# duck_esp.net
KiCad netlist of a schematic drawn in EAGLE
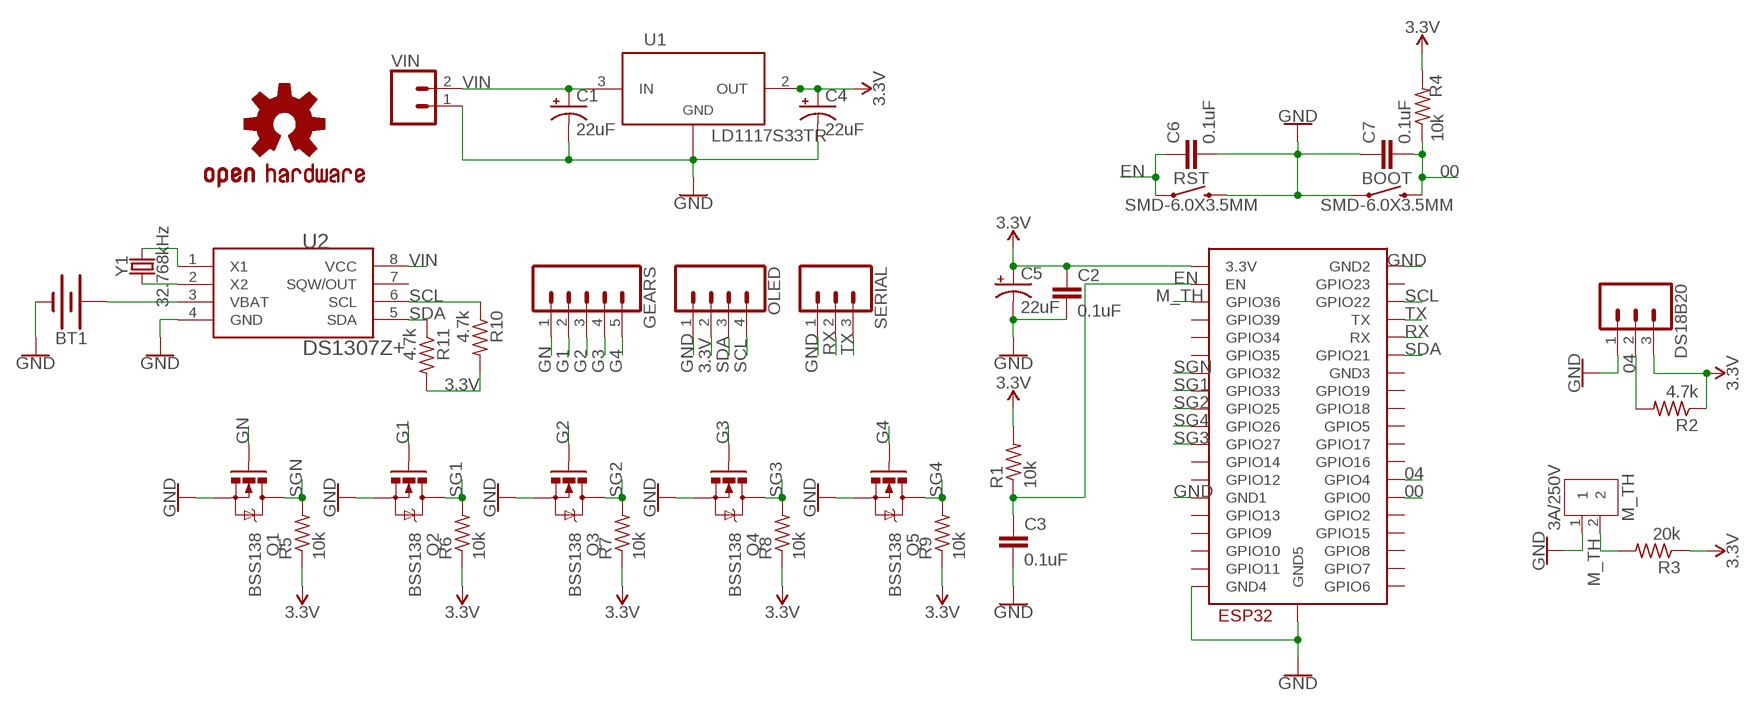
[diagram p0: schematic, sheet 1]

(export (version "E")
  (design (tool "Eeschema 10.0.6"))
  (components
    (comp (ref "BOOT")
      (value "SMD-6.0X3.5MM")
      (footprint "eagle-import:TACTILE_SWITCH_SMD_6.0X3.5MM")
      (libsource (lib "eagle-import") (part "MOMENTARY-SWITCH-SPST-SMD-6.0X3.5MM"))
    )
    (comp (ref "BT1")
      (value "BATTERY-12MM_SMD")
      (footprint "eagle-import:BATTCON_12MM")
      (libsource (lib "eagle-import") (part "BATTERY-12MM_SMD"))
    )
    (comp (ref "C1")
      (value "22uF")
      (footprint "eagle-import:E2-5")
      (libsource (lib "eagle-import") (part "CPOL-USE2-5"))
    )
    (comp (ref "C2")
      (value "0.1uF")
      (footprint "eagle-import:0805")
      (libsource (lib "eagle-import") (part "22UF-0805-6.3V-20%"))
    )
    (comp (ref "C3")
      (value "0.1uF")
      (footprint "eagle-import:0805")
      (libsource (lib "eagle-import") (part "22UF-0805-6.3V-20%"))
    )
    (comp (ref "C4")
      (value "22uF")
      (footprint "eagle-import:E2-5")
      (libsource (lib "eagle-import") (part "CPOL-USE2-5"))
    )
    (comp (ref "C5")
      (value "22uF")
      (footprint "eagle-import:E2-5")
      (libsource (lib "eagle-import") (part "CPOL-USE2-5"))
    )
    (comp (ref "C6")
      (value "0.1uF")
      (footprint "eagle-import:0805")
      (libsource (lib "eagle-import") (part "22UF-0805-6.3V-20%"))
    )
    (comp (ref "C7")
      (value "0.1uF")
      (footprint "eagle-import:0805")
      (libsource (lib "eagle-import") (part "22UF-0805-6.3V-20%"))
    )
    (comp (ref "DS18B20")
      (value "CONN_03")
      (footprint "eagle-import:1X03")
      (libsource (lib "eagle-import") (part "CONN_03"))
    )
    (comp (ref "GEARS")
      (value "CONN_05")
      (footprint "eagle-import:1X05")
      (libsource (lib "eagle-import") (part "CONN_05"))
    )
    (comp (ref "LOGO1")
      (value "OSHW-LOGOL-COPPER")
      (footprint "eagle-import:OSHW-LOGO-L_COPPER")
      (libsource (lib "eagle-import") (part "OSHW-LOGOL-COPPER"))
    )
    (comp (ref "M_TH")
      (value "3A/250V")
      (footprint "eagle-import:B2B-XH-A")
      (fields (field (name "MANUFACTURER") "JST (XH CONNECTOR)") (field (name "MPN") "B2B-XH-A"))
      (libsource (lib "eagle-import") (part "B2B-XH-A"))
    )
    (comp (ref "OLED")
      (value "CONN_04")
      (footprint "eagle-import:1X04")
      (libsource (lib "eagle-import") (part "CONN_04"))
    )
    (comp (ref "Q1")
      (value "BSS138")
      (footprint "eagle-import:SOT23")
      (libsource (lib "eagle-import") (part "MOSFET-NCHANNELBSS138"))
    )
    (comp (ref "Q2")
      (value "BSS138")
      (footprint "eagle-import:SOT23")
      (libsource (lib "eagle-import") (part "MOSFET-NCHANNELBSS138"))
    )
    (comp (ref "Q3")
      (value "BSS138")
      (footprint "eagle-import:SOT23")
      (libsource (lib "eagle-import") (part "MOSFET-NCHANNELBSS138"))
    )
    (comp (ref "Q4")
      (value "BSS138")
      (footprint "eagle-import:SOT23")
      (libsource (lib "eagle-import") (part "MOSFET-NCHANNELBSS138"))
    )
    (comp (ref "Q5")
      (value "BSS138")
      (footprint "eagle-import:SOT23")
      (libsource (lib "eagle-import") (part "MOSFET-NCHANNELBSS138"))
    )
    (comp (ref "R1")
      (value "10k")
      (footprint "eagle-import:R0805")
      (libsource (lib "eagle-import") (part "R-US_R0805"))
    )
    (comp (ref "R2")
      (value "4.7k")
      (footprint "eagle-import:R0805")
      (libsource (lib "eagle-import") (part "R-US_R0805"))
    )
    (comp (ref "R3")
      (value "20k")
      (footprint "eagle-import:R0805")
      (libsource (lib "eagle-import") (part "R-US_R0805"))
    )
    (comp (ref "R4")
      (value "10k")
      (footprint "eagle-import:R0805")
      (libsource (lib "eagle-import") (part "R-US_R0805"))
    )
    (comp (ref "R5")
      (value "10k")
      (footprint "eagle-import:R0805")
      (libsource (lib "eagle-import") (part "R-US_R0805"))
    )
    (comp (ref "R6")
      (value "10k")
      (footprint "eagle-import:R0805")
      (libsource (lib "eagle-import") (part "R-US_R0805"))
    )
    (comp (ref "R7")
      (value "10k")
      (footprint "eagle-import:R0805")
      (libsource (lib "eagle-import") (part "R-US_R0805"))
    )
    (comp (ref "R8")
      (value "10k")
      (footprint "eagle-import:R0805")
      (libsource (lib "eagle-import") (part "R-US_R0805"))
    )
    (comp (ref "R9")
      (value "10k")
      (footprint "eagle-import:R0805")
      (libsource (lib "eagle-import") (part "R-US_R0805"))
    )
    (comp (ref "R10")
      (value "4.7k")
      (footprint "eagle-import:R0805")
      (libsource (lib "eagle-import") (part "R-US_R0805"))
    )
    (comp (ref "R11")
      (value "4.7k")
      (footprint "eagle-import:R0805")
      (libsource (lib "eagle-import") (part "R-US_R0805"))
    )
    (comp (ref "RST")
      (value "SMD-6.0X3.5MM")
      (footprint "eagle-import:TACTILE_SWITCH_SMD_6.0X3.5MM")
      (libsource (lib "eagle-import") (part "MOMENTARY-SWITCH-SPST-SMD-6.0X3.5MM"))
    )
    (comp (ref "SERIAL")
      (value "CONN_03")
      (footprint "eagle-import:1X03")
      (libsource (lib "eagle-import") (part "CONN_03"))
    )
    (comp (ref "U$1")
      (value "ESP32-WROOM")
      (footprint "eagle-import:ESP32-WROOM")
      (libsource (lib "eagle-import") (part "ESP32-WROOM"))
    )
    (comp (ref "U1")
      (value "LD1117S33TR")
      (footprint "eagle-import:SOT-223")
      (fields
        (field (name "DIGIKEY_PART_NUMBER") "497-1242-2-ND")
        (field (name "MANUFACTURER") "STMicroelectronics")
        (field (name "CREATED_BY") "PCBLayout.com")
      )
      (libsource (lib "eagle-import") (part "LD1117S33TR"))
    )
    (comp (ref "U2")
      (value "DS1307Z+")
      (footprint "eagle-import:SOIC-8N")
      (fields
        (field (name "DIGI-KEY_PART_NUMBER") "DS1307Z+-ND")
        (field (name "MANUFACTURER") "Maxim Integrated")
        (field (name "CREATED_BY") "PCBLayout.com")
      )
      (libsource (lib "eagle-import") (part "DS1307Z+"))
    )
    (comp (ref "VIN")
      (value "CONN_02POLAR")
      (footprint "eagle-import:MOLEX-1X2")
      (libsource (lib "eagle-import") (part "CONN_02POLAR"))
    )
    (comp (ref "Y1")
      (value "32.768kHz")
      (footprint "eagle-import:CRYSTAL-SMD-2X6-CYL")
      (libsource (lib "eagle-import") (part "CRYSTAL-32.768KHZSMD-2X6"))
    )
  )
  (nets
    (net (code "1") (name "/00") (class "Default")
      (node (ref "BOOT") (pin "2") (pinfunction "2_2") (pintype "passive"))
      (node (ref "C7") (pin "2") (pinfunction "2_2") (pintype "passive"))
      (node (ref "R4") (pin "1") (pinfunction "1_1") (pintype "passive"))
      (node (ref "U$1") (pin "IO0") (pinfunction "GPIO0_IO0") (pintype "bidirectional"))
    )
    (net (code "2") (name "/04") (class "Default")
      (node (ref "DS18B20") (pin "2") (pinfunction "2_2") (pintype "passive"))
      (node (ref "R2") (pin "2") (pinfunction "2_2") (pintype "passive"))
      (node (ref "U$1") (pin "IO4") (pinfunction "GPIO4_IO4") (pintype "bidirectional"))
    )
    (net (code "3") (name "/EN") (class "Default")
      (node (ref "C3") (pin "1") (pinfunction "1_1") (pintype "passive"))
      (node (ref "C6") (pin "1") (pinfunction "1_1") (pintype "passive"))
      (node (ref "R1") (pin "1") (pinfunction "1_1") (pintype "passive"))
      (node (ref "RST") (pin "1") (pinfunction "1_1") (pintype "passive"))
      (node (ref "U$1") (pin "EN") (pinfunction "EN_EN") (pintype "bidirectional"))
    )
    (net (code "4") (name "/G1") (class "Default")
      (node (ref "GEARS") (pin "2") (pinfunction "2_2") (pintype "passive"))
      (node (ref "Q2") (pin "1") (pinfunction "G_1") (pintype "passive"))
    )
    (net (code "5") (name "/G2") (class "Default")
      (node (ref "GEARS") (pin "3") (pinfunction "3_3") (pintype "passive"))
      (node (ref "Q3") (pin "1") (pinfunction "G_1") (pintype "passive"))
    )
    (net (code "6") (name "/G3") (class "Default")
      (node (ref "GEARS") (pin "4") (pinfunction "4_4") (pintype "passive"))
      (node (ref "Q4") (pin "1") (pinfunction "G_1") (pintype "passive"))
    )
    (net (code "7") (name "/G4") (class "Default")
      (node (ref "GEARS") (pin "5") (pinfunction "5_5") (pintype "passive"))
      (node (ref "Q5") (pin "1") (pinfunction "G_1") (pintype "passive"))
    )
    (net (code "8") (name "/GN") (class "Default")
      (node (ref "GEARS") (pin "1") (pinfunction "1_1") (pintype "passive"))
      (node (ref "Q1") (pin "1") (pinfunction "G_1") (pintype "passive"))
    )
    (net (code "9") (name "/M_TH") (class "Default")
      (node (ref "M_TH") (pin "2") (pinfunction "2_2") (pintype "bidirectional"))
      (node (ref "R3") (pin "2") (pinfunction "2_2") (pintype "passive"))
      (node (ref "U$1") (pin "SENSOR_VP") (pinfunction "GPIO36_SENSOR_VP") (pintype "bidirectional"))
    )
    (net (code "10") (name "/RX") (class "Default")
      (node (ref "SERIAL") (pin "2") (pinfunction "2_2") (pintype "passive"))
      (node (ref "U$1") (pin "RX") (pinfunction "RX_RX") (pintype "bidirectional"))
    )
    (net (code "11") (name "/SCL") (class "Default")
      (node (ref "OLED") (pin "4") (pinfunction "4_4") (pintype "passive"))
      (node (ref "R10") (pin "1") (pinfunction "1_1") (pintype "passive"))
      (node (ref "U$1") (pin "IO22") (pinfunction "GPIO22_IO22") (pintype "bidirectional"))
      (node (ref "U2") (pin "6") (pinfunction "SCL_6") (pintype "input"))
    )
    (net (code "12") (name "/SDA") (class "Default")
      (node (ref "OLED") (pin "3") (pinfunction "3_3") (pintype "passive"))
      (node (ref "R11") (pin "1") (pinfunction "1_1") (pintype "passive"))
      (node (ref "U$1") (pin "IO21") (pinfunction "GPIO21_IO21") (pintype "bidirectional"))
      (node (ref "U2") (pin "5") (pinfunction "SDA_5") (pintype "bidirectional"))
    )
    (net (code "13") (name "/SG1") (class "Default")
      (node (ref "Q2") (pin "3") (pinfunction "D_3") (pintype "passive"))
      (node (ref "R6") (pin "2") (pinfunction "2_2") (pintype "passive"))
      (node (ref "U$1") (pin "IO33") (pinfunction "GPIO33_IO33") (pintype "bidirectional"))
    )
    (net (code "14") (name "/SG2") (class "Default")
      (node (ref "Q3") (pin "3") (pinfunction "D_3") (pintype "passive"))
      (node (ref "R7") (pin "2") (pinfunction "2_2") (pintype "passive"))
      (node (ref "U$1") (pin "IO25") (pinfunction "GPIO25_IO25") (pintype "bidirectional"))
    )
    (net (code "15") (name "/SG3") (class "Default")
      (node (ref "Q4") (pin "3") (pinfunction "D_3") (pintype "passive"))
      (node (ref "R8") (pin "2") (pinfunction "2_2") (pintype "passive"))
      (node (ref "U$1") (pin "IO27") (pinfunction "GPIO27_IO27") (pintype "bidirectional"))
    )
    (net (code "16") (name "/SG4") (class "Default")
      (node (ref "Q5") (pin "3") (pinfunction "D_3") (pintype "passive"))
      (node (ref "R9") (pin "2") (pinfunction "2_2") (pintype "passive"))
      (node (ref "U$1") (pin "IO26") (pinfunction "GPIO26_IO26") (pintype "bidirectional"))
    )
    (net (code "17") (name "/SGN") (class "Default")
      (node (ref "Q1") (pin "3") (pinfunction "D_3") (pintype "passive"))
      (node (ref "R5") (pin "2") (pinfunction "2_2") (pintype "passive"))
      (node (ref "U$1") (pin "IO32") (pinfunction "GPIO32_IO32") (pintype "bidirectional"))
    )
    (net (code "18") (name "/TX") (class "Default")
      (node (ref "SERIAL") (pin "3") (pinfunction "3_3") (pintype "passive"))
      (node (ref "U$1") (pin "TX") (pinfunction "TX_TX") (pintype "bidirectional"))
    )
    (net (code "19") (name "/VIN") (class "Default")
      (node (ref "C1") (pin "+") (pinfunction "+_+") (pintype "passive"))
      (node (ref "U1") (pin "3") (pinfunction "IN_3") (pintype "input"))
      (node (ref "U2") (pin "8") (pinfunction "VCC_8") (pintype "power_in"))
      (node (ref "VIN") (pin "2") (pinfunction "2_2") (pintype "passive"))
    )
    (net (code "20") (name "3.3V") (class "Default")
      (node (ref "C2") (pin "1") (pinfunction "1_1") (pintype "passive"))
      (node (ref "C4") (pin "+") (pinfunction "+_+") (pintype "passive"))
      (node (ref "C5") (pin "+") (pinfunction "+_+") (pintype "passive"))
      (node (ref "DS18B20") (pin "3") (pinfunction "3_3") (pintype "passive"))
      (node (ref "OLED") (pin "2") (pinfunction "2_2") (pintype "passive"))
      (node (ref "R1") (pin "2") (pinfunction "2_2") (pintype "passive"))
      (node (ref "R10") (pin "2") (pinfunction "2_2") (pintype "passive"))
      (node (ref "R11") (pin "2") (pinfunction "2_2") (pintype "passive"))
      (node (ref "R2") (pin "1") (pinfunction "1_1") (pintype "passive"))
      (node (ref "R3") (pin "1") (pinfunction "1_1") (pintype "passive"))
      (node (ref "R4") (pin "2") (pinfunction "2_2") (pintype "passive"))
      (node (ref "R5") (pin "1") (pinfunction "1_1") (pintype "passive"))
      (node (ref "R6") (pin "1") (pinfunction "1_1") (pintype "passive"))
      (node (ref "R7") (pin "1") (pinfunction "1_1") (pintype "passive"))
      (node (ref "R8") (pin "1") (pinfunction "1_1") (pintype "passive"))
      (node (ref "R9") (pin "1") (pinfunction "1_1") (pintype "passive"))
      (node (ref "U$1") (pin "3V3") (pinfunction "3.3V_3V3") (pintype "bidirectional"))
      (node (ref "U1") (pin "2") (pinfunction "OUT_2") (pintype "output"))
      (node (ref "U1") (pin "4") (pinfunction "4_4") (pintype "passive"))
    )
    (net (code "21") (name "GND") (class "Default")
      (node (ref "BOOT") (pin "1") (pinfunction "1_1") (pintype "passive"))
      (node (ref "BT1") (pin "GND") (pinfunction "-_GND") (pintype "power_in"))
      (node (ref "C1") (pin "-") (pinfunction "-_-") (pintype "passive"))
      (node (ref "C2") (pin "2") (pinfunction "2_2") (pintype "passive"))
      (node (ref "C3") (pin "2") (pinfunction "2_2") (pintype "passive"))
      (node (ref "C4") (pin "-") (pinfunction "-_-") (pintype "passive"))
      (node (ref "C5") (pin "-") (pinfunction "-_-") (pintype "passive"))
      (node (ref "C6") (pin "2") (pinfunction "2_2") (pintype "passive"))
      (node (ref "C7") (pin "1") (pinfunction "1_1") (pintype "passive"))
      (node (ref "DS18B20") (pin "1") (pinfunction "1_1") (pintype "passive"))
      (node (ref "M_TH") (pin "1") (pinfunction "1_1") (pintype "bidirectional"))
      (node (ref "OLED") (pin "1") (pinfunction "1_1") (pintype "passive"))
      (node (ref "Q1") (pin "2") (pinfunction "S_2") (pintype "passive"))
      (node (ref "Q2") (pin "2") (pinfunction "S_2") (pintype "passive"))
      (node (ref "Q3") (pin "2") (pinfunction "S_2") (pintype "passive"))
      (node (ref "Q4") (pin "2") (pinfunction "S_2") (pintype "passive"))
      (node (ref "Q5") (pin "2") (pinfunction "S_2") (pintype "passive"))
      (node (ref "RST") (pin "2") (pinfunction "2_2") (pintype "passive"))
      (node (ref "SERIAL") (pin "1") (pinfunction "1_1") (pintype "passive"))
      (node (ref "U$1") (pin "GND1") (pinfunction "GND1_GND1") (pintype "bidirectional"))
      (node (ref "U$1") (pin "GND2") (pinfunction "GND2_GND2") (pintype "bidirectional"))
      (node (ref "U$1") (pin "GND4") (pinfunction "GND4_GND4") (pintype "bidirectional"))
      (node (ref "U$1") (pin "GND5") (pinfunction "GND5_GND5") (pintype "bidirectional"))
      (node (ref "U1") (pin "1") (pinfunction "ADJ/GND_1") (pintype "power_in"))
      (node (ref "U2") (pin "4") (pinfunction "GND_4") (pintype "power_in"))
      (node (ref "VIN") (pin "1") (pinfunction "1_1") (pintype "passive"))
    )
    (net (code "22") (name "Net-(BT1-+)") (class "Default")
      (node (ref "BT1") (pin "PWR@1") (pinfunction "+_PWR@1") (pintype "power_in"))
      (node (ref "U2") (pin "3") (pinfunction "VBAT_3") (pintype "power_in"))
    )
    (net (code "23") (name "Net-(U2-X1)") (class "Default")
      (node (ref "U2") (pin "1") (pinfunction "X1_1") (pintype "passive"))
      (node (ref "Y1") (pin "X2") (pinfunction "2_X2") (pintype "passive"))
    )
    (net (code "24") (name "Net-(U2-X2)") (class "Default")
      (node (ref "U2") (pin "2") (pinfunction "X2_2") (pintype "passive"))
      (node (ref "Y1") (pin "X1") (pinfunction "1_X1") (pintype "passive"))
    )
    (net (code "25") (name "unconnected-(U$1-GPIO2-PadIO2)") (class "Default")
      (node (ref "U$1") (pin "IO2") (pinfunction "GPIO2_IO2") (pintype "bidirectional"))
    )
    (net (code "26") (name "unconnected-(U$1-GPIO5-PadIO5)") (class "Default")
      (node (ref "U$1") (pin "IO5") (pinfunction "GPIO5_IO5") (pintype "bidirectional"))
    )
    (net (code "27") (name "unconnected-(U$1-GPIO6-PadCLK)") (class "Default")
      (node (ref "U$1") (pin "CLK") (pinfunction "GPIO6_CLK") (pintype "bidirectional"))
    )
    (net (code "28") (name "unconnected-(U$1-GPIO7-PadSD0)") (class "Default")
      (node (ref "U$1") (pin "SD0") (pinfunction "GPIO7_SD0") (pintype "bidirectional"))
    )
    (net (code "29") (name "unconnected-(U$1-GPIO8-PadSD1)") (class "Default")
      (node (ref "U$1") (pin "SD1") (pinfunction "GPIO8_SD1") (pintype "bidirectional"))
    )
    (net (code "30") (name "unconnected-(U$1-GPIO9-PadSD2)") (class "Default")
      (node (ref "U$1") (pin "SD2") (pinfunction "GPIO9_SD2") (pintype "bidirectional"))
    )
    (net (code "31") (name "unconnected-(U$1-GPIO10-PadSD3)") (class "Default")
      (node (ref "U$1") (pin "SD3") (pinfunction "GPIO10_SD3") (pintype "bidirectional"))
    )
    (net (code "32") (name "unconnected-(U$1-GPIO11-PadCMD)") (class "Default")
      (node (ref "U$1") (pin "CMD") (pinfunction "GPIO11_CMD") (pintype "bidirectional"))
    )
    (net (code "33") (name "unconnected-(U$1-GPIO12-PadIO12)") (class "Default")
      (node (ref "U$1") (pin "IO12") (pinfunction "GPIO12_IO12") (pintype "bidirectional"))
    )
    (net (code "34") (name "unconnected-(U$1-GPIO13-PadIO13)") (class "Default")
      (node (ref "U$1") (pin "IO13") (pinfunction "GPIO13_IO13") (pintype "bidirectional"))
    )
    (net (code "35") (name "unconnected-(U$1-GPIO14-PadIO14)") (class "Default")
      (node (ref "U$1") (pin "IO14") (pinfunction "GPIO14_IO14") (pintype "bidirectional"))
    )
    (net (code "36") (name "unconnected-(U$1-GPIO15-PadIO15)") (class "Default")
      (node (ref "U$1") (pin "IO15") (pinfunction "GPIO15_IO15") (pintype "bidirectional"))
    )
    (net (code "37") (name "unconnected-(U$1-GPIO16-PadIO16)") (class "Default")
      (node (ref "U$1") (pin "IO16") (pinfunction "GPIO16_IO16") (pintype "bidirectional"))
    )
    (net (code "38") (name "unconnected-(U$1-GPIO17-PadIO17)") (class "Default")
      (node (ref "U$1") (pin "IO17") (pinfunction "GPIO17_IO17") (pintype "bidirectional"))
    )
    (net (code "39") (name "unconnected-(U$1-GPIO18-PadIO18)") (class "Default")
      (node (ref "U$1") (pin "IO18") (pinfunction "GPIO18_IO18") (pintype "bidirectional"))
    )
    (net (code "40") (name "unconnected-(U$1-GPIO19-PadIO19)") (class "Default")
      (node (ref "U$1") (pin "IO19") (pinfunction "GPIO19_IO19") (pintype "bidirectional"))
    )
    (net (code "41") (name "unconnected-(U$1-GPIO23-PadIO23)") (class "Default")
      (node (ref "U$1") (pin "IO23") (pinfunction "GPIO23_IO23") (pintype "bidirectional"))
    )
    (net (code "42") (name "unconnected-(U$1-GPIO34-PadIO34)") (class "Default")
      (node (ref "U$1") (pin "IO34") (pinfunction "GPIO34_IO34") (pintype "bidirectional"))
    )
    (net (code "43") (name "unconnected-(U$1-GPIO35-PadIO35)") (class "Default")
      (node (ref "U$1") (pin "IO35") (pinfunction "GPIO35_IO35") (pintype "bidirectional"))
    )
    (net (code "44") (name "unconnected-(U$1-GPIO39-PadSENSOR_VN)") (class "Default")
      (node (ref "U$1") (pin "SENSOR_VN") (pinfunction "GPIO39_SENSOR_VN") (pintype "bidirectional"))
    )
    (net (code "45") (name "unconnected-(U$1-PadGND3)") (class "Default")
      (node (ref "U$1") (pin "GND3") (pinfunction "GND3_GND3") (pintype "bidirectional"))
    )
    (net (code "46") (name "unconnected-(U2-SQW{slash}OUT-Pad7)") (class "Default")
      (node (ref "U2") (pin "7") (pinfunction "SQW/OUT_7") (pintype "output"))
    )
  )
)
